# motorized_potentiometer.net
KiCad netlist of a schematic drawn in EAGLE
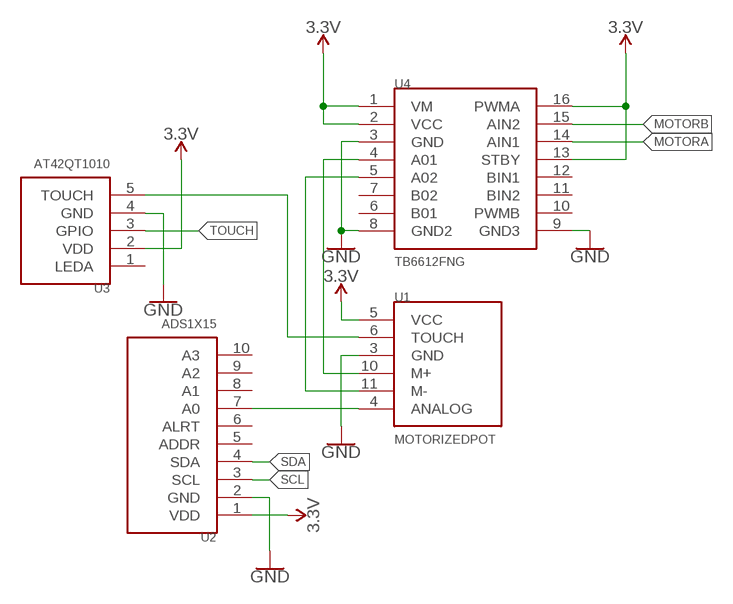
[diagram p0: schematic, sheet 1]

(export (version "E")
  (design (tool "Eeschema 10.0.6"))
  (components
    (comp (ref "U1")
      (value "MOTORIZEDPOT")
      (footprint "eagle-import:MOTORIZEDPOT")
      (libsource (lib "eagle-import") (part "MOTORIZEDPOT"))
    )
    (comp (ref "U2")
      (value "ADS1X15")
      (footprint "eagle-import:ADS1X15")
      (libsource (lib "eagle-import") (part "ADS1X15"))
    )
    (comp (ref "U3")
      (value "AT42QT1010")
      (footprint "eagle-import:AT42QT1010")
      (libsource (lib "eagle-import") (part "AT42QT1010"))
    )
    (comp (ref "U4")
      (value "TB6612FNG")
      (footprint "eagle-import:TB6612FNG")
      (libsource (lib "eagle-import") (part "TB6612FNG"))
    )
  )
  (nets
    (net (code "1") (name "3.3V") (class "Default")
      (node (ref "U1") (pin "5") (pinfunction "VCC_5") (pintype "bidirectional"))
      (node (ref "U2") (pin "1") (pinfunction "VDD_1") (pintype "bidirectional"))
      (node (ref "U3") (pin "2") (pinfunction "VDD_2") (pintype "bidirectional"))
      (node (ref "U4") (pin "1") (pinfunction "VM_1") (pintype "bidirectional"))
      (node (ref "U4") (pin "13") (pinfunction "STBY_13") (pintype "bidirectional"))
      (node (ref "U4") (pin "16") (pinfunction "PWMA_16") (pintype "bidirectional"))
      (node (ref "U4") (pin "2") (pinfunction "VCC_2") (pintype "bidirectional"))
    )
    (net (code "2") (name "GND") (class "Default")
      (node (ref "U1") (pin "3") (pinfunction "GND_3") (pintype "bidirectional"))
      (node (ref "U2") (pin "2") (pinfunction "GND_2") (pintype "bidirectional"))
      (node (ref "U3") (pin "4") (pinfunction "GND_4") (pintype "bidirectional"))
      (node (ref "U4") (pin "3") (pinfunction "GND_3") (pintype "bidirectional"))
      (node (ref "U4") (pin "8") (pinfunction "GND2_8") (pintype "bidirectional"))
      (node (ref "U4") (pin "9") (pinfunction "GND3_9") (pintype "bidirectional"))
    )
    (net (code "3") (name "MOTORA") (class "Default")
      (node (ref "U4") (pin "14") (pinfunction "AIN1_14") (pintype "bidirectional"))
    )
    (net (code "4") (name "MOTORB") (class "Default")
      (node (ref "U4") (pin "15") (pinfunction "AIN2_15") (pintype "bidirectional"))
    )
    (net (code "5") (name "Net-(U1-ANALOG)") (class "Default")
      (node (ref "U1") (pin "4") (pinfunction "ANALOG_4") (pintype "bidirectional"))
      (node (ref "U2") (pin "7") (pinfunction "A0_7") (pintype "bidirectional"))
    )
    (net (code "6") (name "Net-(U1-M+)") (class "Default")
      (node (ref "U1") (pin "10") (pinfunction "M+_10") (pintype "bidirectional"))
      (node (ref "U4") (pin "4") (pinfunction "A01_4") (pintype "bidirectional"))
    )
    (net (code "7") (name "Net-(U1-M-)") (class "Default")
      (node (ref "U1") (pin "11") (pinfunction "M-_11") (pintype "bidirectional"))
      (node (ref "U4") (pin "5") (pinfunction "A02_5") (pintype "bidirectional"))
    )
    (net (code "8") (name "Net-(U1-TOUCH)") (class "Default")
      (node (ref "U1") (pin "6") (pinfunction "TOUCH_6") (pintype "bidirectional"))
      (node (ref "U3") (pin "5") (pinfunction "TOUCH_5") (pintype "bidirectional"))
    )
    (net (code "9") (name "SCL") (class "Default")
      (node (ref "U2") (pin "3") (pinfunction "SCL_3") (pintype "bidirectional"))
    )
    (net (code "10") (name "SDA") (class "Default")
      (node (ref "U2") (pin "4") (pinfunction "SDA_4") (pintype "bidirectional"))
    )
    (net (code "11") (name "TOUCH") (class "Default")
      (node (ref "U3") (pin "3") (pinfunction "GPIO_3") (pintype "bidirectional"))
    )
    (net (code "12") (name "unconnected-(U2-A1-Pad8)") (class "Default")
      (node (ref "U2") (pin "8") (pinfunction "A1_8") (pintype "bidirectional"))
    )
    (net (code "13") (name "unconnected-(U2-A2-Pad9)") (class "Default")
      (node (ref "U2") (pin "9") (pinfunction "A2_9") (pintype "bidirectional"))
    )
    (net (code "14") (name "unconnected-(U2-A3-Pad10)") (class "Default")
      (node (ref "U2") (pin "10") (pinfunction "A3_10") (pintype "bidirectional"))
    )
    (net (code "15") (name "unconnected-(U2-ADDR-Pad5)") (class "Default")
      (node (ref "U2") (pin "5") (pinfunction "ADDR_5") (pintype "bidirectional"))
    )
    (net (code "16") (name "unconnected-(U2-ALRT-Pad6)") (class "Default")
      (node (ref "U2") (pin "6") (pinfunction "ALRT_6") (pintype "bidirectional"))
    )
    (net (code "17") (name "unconnected-(U3-LEDA-Pad1)") (class "Default")
      (node (ref "U3") (pin "1") (pinfunction "LEDA_1") (pintype "bidirectional"))
    )
    (net (code "18") (name "unconnected-(U4-B01-Pad6)") (class "Default")
      (node (ref "U4") (pin "6") (pinfunction "B01_6") (pintype "bidirectional"))
    )
    (net (code "19") (name "unconnected-(U4-B02-Pad7)") (class "Default")
      (node (ref "U4") (pin "7") (pinfunction "B02_7") (pintype "bidirectional"))
    )
    (net (code "20") (name "unconnected-(U4-BIN1-Pad12)") (class "Default")
      (node (ref "U4") (pin "12") (pinfunction "BIN1_12") (pintype "bidirectional"))
    )
    (net (code "21") (name "unconnected-(U4-BIN2-Pad11)") (class "Default")
      (node (ref "U4") (pin "11") (pinfunction "BIN2_11") (pintype "bidirectional"))
    )
    (net (code "22") (name "unconnected-(U4-PWMB-Pad10)") (class "Default")
      (node (ref "U4") (pin "10") (pinfunction "PWMB_10") (pintype "bidirectional"))
    )
  )
)
